# Power.net
KiCad netlist of a schematic drawn in Altium Designer
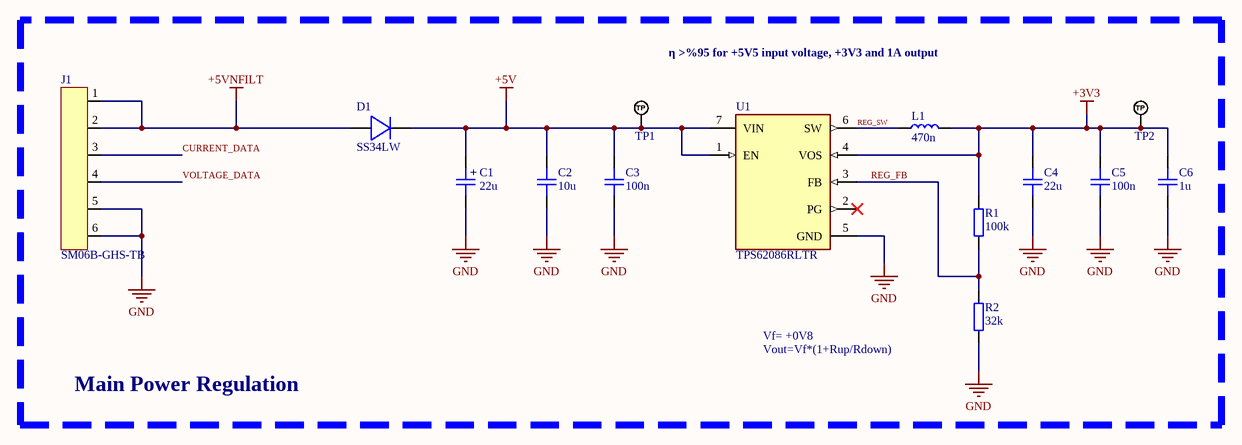
[diagram p0: Power.SchDoc]

(export (version "E")
  (design (tool "Eeschema 10.0.6"))
  (components
    (comp (ref "C1")
      (value "22u")
      (footprint "CAP_AE_SMD_D6MM3_H5M55")
      (description "Capacitor SMD Aluminium Electrolytic 6.3mm Diameter 5.5mm Height")
      (libsource (lib "Schematic-Lib-PhilsLab") (part "CAP_ALEL_6.3x5.5"))
    )
    (comp (ref "C2")
      (value "10u")
      (footprint "CAP_1206")
      (description "Capacitor SMD 1206")
      (libsource (lib "Schematic-Lib-PhilsLab") (part "CAP_1206"))
    )
    (comp (ref "C3")
      (value "100n")
      (footprint "CAP_0402")
      (description "Capacitor SMD 0402")
      (libsource (lib "Schematic-Lib-PhilsLab") (part "CAP_0402"))
    )
    (comp (ref "C4")
      (value "22u")
      (footprint "CAP_1210")
      (description "Capacitor SMD 1210")
      (libsource (lib "Schematic-Lib-PhilsLab") (part "CAP_1210"))
    )
    (comp (ref "C5")
      (value "100n")
      (footprint "CAP_0402")
      (description "Capacitor SMD 0402")
      (libsource (lib "Schematic-Lib-PhilsLab") (part "CAP_0402"))
    )
    (comp (ref "C6")
      (value "1u")
      (footprint "CAP_0402")
      (description "Capacitor SMD 0402")
      (libsource (lib "Schematic-Lib-PhilsLab") (part "CAP_0402"))
    )
    (comp (ref "D1")
      (value "SS34LW")
      (footprint "SOD-123W")
      (description "3A, 40V - 200V Schottky Barrier Surface Mount Rectifier")
      (libsource (lib "AltiumSchLib") (part "SS34LW"))
    )
    (comp (ref "J1")
      (value "SM06B-GHS-TB")
      (footprint "SM06B-GHS-TB")
      (description "Header Connector 6 Position 1.25MM Pitch SMD Horizontal JST GH")
      (fields (field (name "MANUFACTURER") "JST"))
      (libsource (lib "Schematic-Lib-PhilsLab") (part "SM06B-GHS-TB"))
    )
    (comp (ref "L1")
      (value "470n")
      (footprint "IND_1008")
      (description "Inductor SMD 1008")
      (libsource (lib "Schematic-Lib-PhilsLab") (part "IND_1008"))
    )
    (comp (ref "R1")
      (value "100k")
      (footprint "RES_0402")
      (description "Resistor SMD 0402")
      (libsource (lib "Schematic-Lib-PhilsLab") (part "RES_0402"))
    )
    (comp (ref "R2")
      (value "32k")
      (footprint "RES_0402")
      (description "Resistor SMD 0402")
      (libsource (lib "Schematic-Lib-PhilsLab") (part "RES_0402"))
    )
    (comp (ref "TP1")
      (value "TP_NOBOM")
      (footprint "PAD_RND_1MM")
      (description "Test Point Round 1mm (NO BOM)")
      (libsource (lib "Schematic-Lib-PhilsLab") (part "TEST_POINT_RND_1MM"))
    )
    (comp (ref "TP2")
      (value "TP_NOBOM")
      (footprint "PAD_RND_1MM")
      (description "Test Point Round 1mm (NO BOM)")
      (libsource (lib "Schematic-Lib-PhilsLab") (part "TEST_POINT_RND_1MM"))
    )
    (comp (ref "U1")
      (value "TPS62086RLTR")
      (footprint "FP-RLT0007A-MFG")
      (description "IC REG BUCK 3.3V 3A 7VSON-HR")
      (libsource (lib "Altium Content Vault") (part "4e7eb6474dc88d883a1c2f1f1891d8c"))
    )
  )
  (nets
    (net (code "1") (name "+3V3") (class "Default")
      (node (ref "C4") (pin "2") (pinfunction "2_2") (pintype "passive"))
      (node (ref "C5") (pin "2") (pinfunction "2_2") (pintype "passive"))
      (node (ref "C6") (pin "2") (pinfunction "2_2") (pintype "passive"))
      (node (ref "L1") (pin "2") (pinfunction "2_2") (pintype "passive"))
      (node (ref "R1") (pin "2") (pinfunction "2_2") (pintype "passive"))
      (node (ref "TP2") (pin "1") (pinfunction "TP_1") (pintype "passive"))
      (node (ref "U1") (pin "4") (pinfunction "VOS_4") (pintype "input"))
    )
    (net (code "2") (name "+5V") (class "Default")
      (node (ref "C1") (pin "1") (pinfunction "1_1") (pintype "passive"))
      (node (ref "C2") (pin "2") (pinfunction "2_2") (pintype "passive"))
      (node (ref "C3") (pin "2") (pinfunction "2_2") (pintype "passive"))
      (node (ref "D1") (pin "2") (pinfunction "2_2") (pintype "power_in"))
      (node (ref "TP1") (pin "1") (pinfunction "TP_1") (pintype "passive"))
      (node (ref "U1") (pin "1") (pinfunction "EN_1") (pintype "input"))
      (node (ref "U1") (pin "7") (pinfunction "VIN_7") (pintype "power_in"))
    )
    (net (code "3") (name "+5VNFILT") (class "Default")
      (node (ref "D1") (pin "1") (pinfunction "1_1") (pintype "power_in"))
      (node (ref "J1") (pin "1") (pinfunction "1_1") (pintype "passive"))
      (node (ref "J1") (pin "2") (pinfunction "2_2") (pintype "passive"))
    )
    (net (code "4") (name "/CURRENT_DATA") (class "Default")
      (node (ref "J1") (pin "3") (pinfunction "3_3") (pintype "passive"))
    )
    (net (code "5") (name "/REG_FB") (class "Default")
      (node (ref "R1") (pin "1") (pinfunction "1_1") (pintype "passive"))
      (node (ref "R2") (pin "2") (pinfunction "2_2") (pintype "passive"))
      (node (ref "U1") (pin "3") (pinfunction "FB_3") (pintype "input"))
    )
    (net (code "6") (name "/REG_SW") (class "Default")
      (node (ref "L1") (pin "1") (pinfunction "1_1") (pintype "passive"))
      (node (ref "U1") (pin "6") (pinfunction "SW_6") (pintype "output"))
    )
    (net (code "7") (name "/VOLTAGE_DATA") (class "Default")
      (node (ref "J1") (pin "4") (pinfunction "4_4") (pintype "passive"))
    )
    (net (code "8") (name "GND") (class "Default")
      (node (ref "C1") (pin "2") (pinfunction "2_2") (pintype "passive"))
      (node (ref "C2") (pin "1") (pinfunction "1_1") (pintype "passive"))
      (node (ref "C3") (pin "1") (pinfunction "1_1") (pintype "passive"))
      (node (ref "C4") (pin "1") (pinfunction "1_1") (pintype "passive"))
      (node (ref "C5") (pin "1") (pinfunction "1_1") (pintype "passive"))
      (node (ref "C6") (pin "1") (pinfunction "1_1") (pintype "passive"))
      (node (ref "J1") (pin "5") (pinfunction "5_5") (pintype "passive"))
      (node (ref "J1") (pin "6") (pinfunction "6_6") (pintype "passive"))
      (node (ref "R2") (pin "1") (pinfunction "1_1") (pintype "passive"))
      (node (ref "U1") (pin "5") (pinfunction "GND_5") (pintype "power_in"))
    )
    (net (code "9") (name "unconnected-(U1-PG-Pad2)") (class "Default")
      (node (ref "U1") (pin "2") (pinfunction "PG_2") (pintype "output+no_connect"))
    )
  )
)
